# pylontec_mqttinterface1b.net
KiCad netlist of a schematic drawn in EAGLE
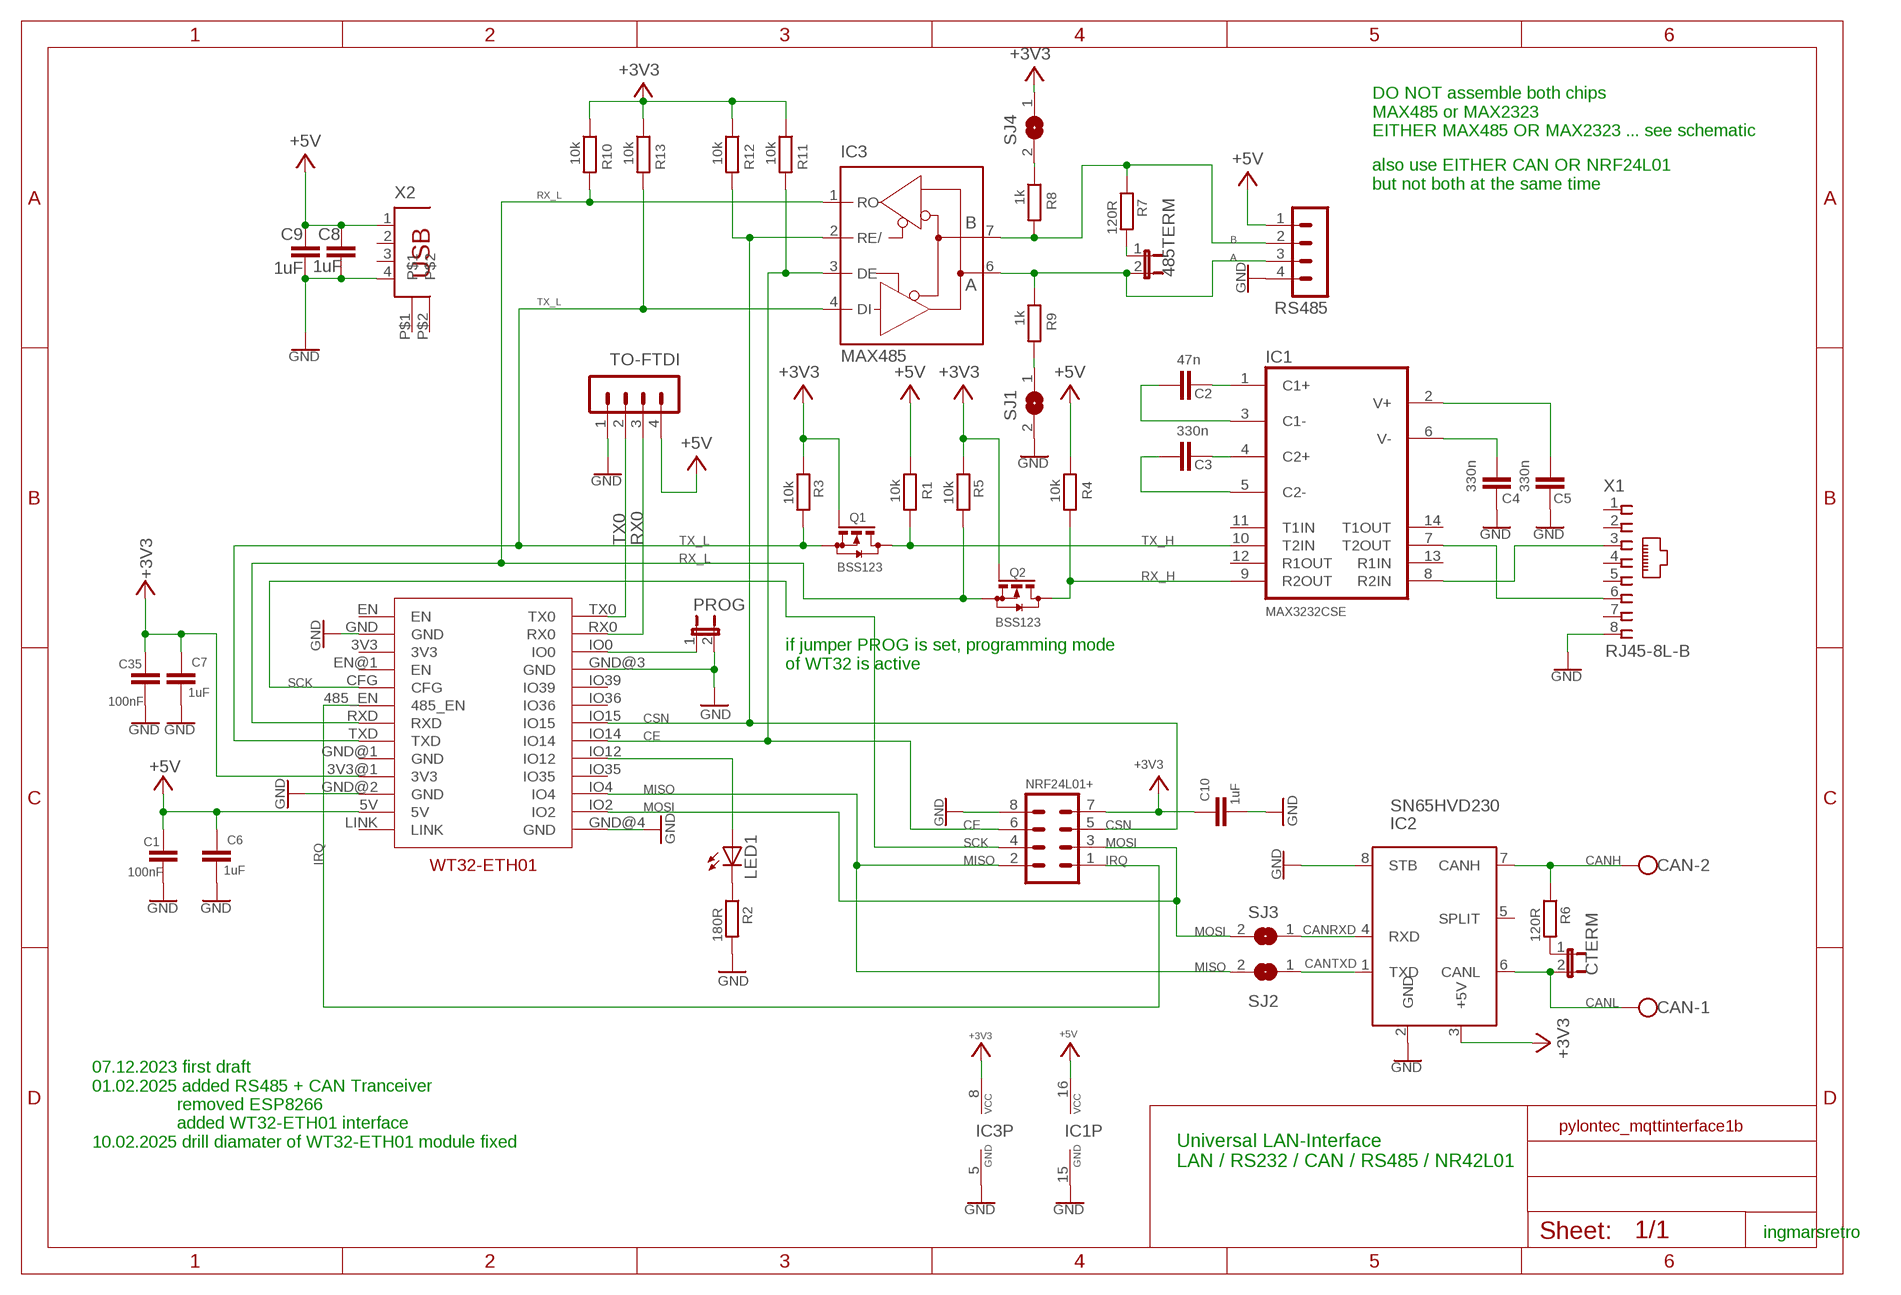
[diagram p0: schematic, sheet 1]

(export (version "E")
  (design (tool "Eeschema 10.0.6"))
  (components
    (comp (ref "485TERM")
      (value "JP1E")
      (footprint "eagle-import:JP1")
      (libsource (lib "eagle-import") (part "JP1E"))
    )
    (comp (ref "C1")
      (value "100nF")
      (footprint "eagle-import:C0805")
      (libsource (lib "eagle-import") (part "resistor_C-EUC0805"))
    )
    (comp (ref "C2")
      (value "47n")
      (footprint "eagle-import:C0805")
      (libsource (lib "eagle-import") (part "resistor_C-EUC0805"))
    )
    (comp (ref "C3")
      (value "330n")
      (footprint "eagle-import:C0805")
      (libsource (lib "eagle-import") (part "resistor_C-EUC0805"))
    )
    (comp (ref "C4")
      (value "330n")
      (footprint "eagle-import:C0805")
      (libsource (lib "eagle-import") (part "resistor_C-EUC0805"))
    )
    (comp (ref "C5")
      (value "330n")
      (footprint "eagle-import:C0805")
      (libsource (lib "eagle-import") (part "resistor_C-EUC0805"))
    )
    (comp (ref "C6")
      (value "1uF")
      (footprint "eagle-import:C1210")
      (libsource (lib "eagle-import") (part "C-EUC1210"))
    )
    (comp (ref "C7")
      (value "1uF")
      (footprint "eagle-import:C1210")
      (libsource (lib "eagle-import") (part "C-EUC1210"))
    )
    (comp (ref "C8")
      (value "1uF")
      (footprint "eagle-import:C1210")
      (libsource (lib "eagle-import") (part "C-EUC1210"))
    )
    (comp (ref "C9")
      (value "1uF")
      (footprint "eagle-import:C1210")
      (libsource (lib "eagle-import") (part "C-EUC1210"))
    )
    (comp (ref "C10")
      (value "1uF")
      (footprint "eagle-import:C1210")
      (libsource (lib "eagle-import") (part "C-EUC1210"))
    )
    (comp (ref "C35")
      (value "100nF")
      (footprint "eagle-import:C0805")
      (libsource (lib "eagle-import") (part "resistor_C-EUC0805"))
    )
    (comp (ref "CAN")
      (value "W237-102")
      (footprint "eagle-import:W237-102")
      (fields (field (name "MPN") "237-102"))
      (libsource (lib "eagle-import") (part "W237-102"))
    )
    (comp (ref "CTERM")
      (value "JP1E")
      (footprint "eagle-import:JP1")
      (libsource (lib "eagle-import") (part "JP1E"))
    )
    (comp (ref "IC1")
      (value "MAX3232CSE")
      (footprint "eagle-import:SO16")
      (libsource (lib "eagle-import") (part "MAX3232SEC"))
    )
    (comp (ref "IC2")
      (value "SN65HVD230")
      (footprint "eagle-import:SO8")
      (libsource (lib "eagle-import") (part "TJA1040"))
    )
    (comp (ref "IC3")
      (value "MAX485")
      (footprint "eagle-import:SO08")
      (fields (field (name "MF") "MAXIM") (field (name "MPN") "MAX481CSA"))
      (libsource (lib "eagle-import") (part "MAX481CSA"))
    )
    (comp (ref "LED1")
      (value "LED_LEDCHIPLED_0805")
      (footprint "eagle-import:LED_CHIPLED_0805")
      (libsource (lib "eagle-import") (part "LED_LEDCHIPLED_0805"))
    )
    (comp (ref "NRF24L01+")
      (value "MA04-2")
      (footprint "eagle-import:MA04-2")
      (libsource (lib "eagle-import") (part "MA04-2"))
    )
    (comp (ref "PROG")
      (value "JP1E")
      (footprint "eagle-import:JP1")
      (libsource (lib "eagle-import") (part "JP1E"))
    )
    (comp (ref "Q1")
      (value "BSS123")
      (footprint "eagle-import:SOT23")
      (libsource (lib "eagle-import") (part "BSS123"))
    )
    (comp (ref "Q2")
      (value "BSS123")
      (footprint "eagle-import:SOT23")
      (libsource (lib "eagle-import") (part "BSS123"))
    )
    (comp (ref "R1")
      (value "10k")
      (footprint "eagle-import:R0805")
      (libsource (lib "eagle-import") (part "R-EU_R0805"))
    )
    (comp (ref "R2")
      (value "180R")
      (footprint "eagle-import:R0805")
      (libsource (lib "eagle-import") (part "R-EU_R0805"))
    )
    (comp (ref "R3")
      (value "10k")
      (footprint "eagle-import:R0805")
      (libsource (lib "eagle-import") (part "R-EU_R0805"))
    )
    (comp (ref "R4")
      (value "10k")
      (footprint "eagle-import:R0805")
      (libsource (lib "eagle-import") (part "R-EU_R0805"))
    )
    (comp (ref "R5")
      (value "10k")
      (footprint "eagle-import:R0805")
      (libsource (lib "eagle-import") (part "R-EU_R0805"))
    )
    (comp (ref "R6")
      (value "120R")
      (footprint "eagle-import:R0805")
      (libsource (lib "eagle-import") (part "R-EU_R0805"))
    )
    (comp (ref "R7")
      (value "120R")
      (footprint "eagle-import:R0805")
      (libsource (lib "eagle-import") (part "R-EU_R0805"))
    )
    (comp (ref "R8")
      (value "1k")
      (footprint "eagle-import:R0805")
      (libsource (lib "eagle-import") (part "R-EU_R0805"))
    )
    (comp (ref "R9")
      (value "1k")
      (footprint "eagle-import:R0805")
      (libsource (lib "eagle-import") (part "R-EU_R0805"))
    )
    (comp (ref "R10")
      (value "10k")
      (footprint "eagle-import:R0805")
      (libsource (lib "eagle-import") (part "R-EU_R0805"))
    )
    (comp (ref "R11")
      (value "10k")
      (footprint "eagle-import:R0805")
      (libsource (lib "eagle-import") (part "R-EU_R0805"))
    )
    (comp (ref "R12")
      (value "10k")
      (footprint "eagle-import:R0805")
      (libsource (lib "eagle-import") (part "R-EU_R0805"))
    )
    (comp (ref "R13")
      (value "10k")
      (footprint "eagle-import:R0805")
      (libsource (lib "eagle-import") (part "R-EU_R0805"))
    )
    (comp (ref "RS485")
      (value "MA04-1")
      (footprint "eagle-import:MA04-1")
      (libsource (lib "eagle-import") (part "MA04-1"))
    )
    (comp (ref "SJ1") (value "SJ") (footprint "eagle-import:SJ") (libsource (lib "eagle-import") (part "SJ")))
    (comp (ref "SJ2") (value "SJ") (footprint "eagle-import:SJ") (libsource (lib "eagle-import") (part "SJ")))
    (comp (ref "SJ3") (value "SJ") (footprint "eagle-import:SJ") (libsource (lib "eagle-import") (part "SJ")))
    (comp (ref "SJ4") (value "SJ") (footprint "eagle-import:SJ") (libsource (lib "eagle-import") (part "SJ")))
    (comp (ref "TO-FTDI")
      (value "MA04-1")
      (footprint "eagle-import:MA04-1")
      (libsource (lib "eagle-import") (part "MA04-1"))
    )
    (comp (ref "U$2")
      (value "WT32-ETH01")
      (footprint "eagle-import:WT32-ETH01")
      (fields (field (name "MF") "wireless-tag"))
      (libsource (lib "eagle-import") (part "WT32-ETH01"))
    )
    (comp (ref "X1")
      (value "RJ45-8L-B")
      (footprint "eagle-import:RJ45-NO-SHIELD")
      (fields (field (name "MF") "TYCO ELECTRONICS"))
      (libsource (lib "eagle-import") (part "RJ45-8L-B"))
    )
    (comp (ref "X2")
      (value "SMARTPRJ_PN61729")
      (footprint "eagle-import:SMARTPRJ_PN61729")
      (libsource (lib "eagle-import") (part "SMARTPRJ_PN61729"))
    )
  )
  (nets
    (net (code "1") (name "+3V3") (class "Default")
      (node (ref "C10") (pin "1") (pinfunction "1_1") (pintype "passive"))
      (node (ref "C35") (pin "2") (pinfunction "2_2") (pintype "passive"))
      (node (ref "C7") (pin "1") (pinfunction "1_1") (pintype "passive"))
      (node (ref "IC2") (pin "3") (pinfunction "+5V_3") (pintype "bidirectional"))
      (node (ref "IC3") (pin "8") (pinfunction "VCC_8") (pintype "power_in"))
      (node (ref "NRF24L01+") (pin "7") (pinfunction "7_7") (pintype "passive"))
      (node (ref "Q1") (pin "1") (pinfunction "G_1") (pintype "passive"))
      (node (ref "Q2") (pin "1") (pinfunction "G_1") (pintype "passive"))
      (node (ref "R10") (pin "1") (pinfunction "1_1") (pintype "passive"))
      (node (ref "R11") (pin "1") (pinfunction "1_1") (pintype "passive"))
      (node (ref "R12") (pin "1") (pinfunction "1_1") (pintype "passive"))
      (node (ref "R13") (pin "1") (pinfunction "1_1") (pintype "passive"))
      (node (ref "R3") (pin "1") (pinfunction "1_1") (pintype "passive"))
      (node (ref "R5") (pin "1") (pinfunction "1_1") (pintype "passive"))
      (node (ref "SJ4") (pin "1") (pinfunction "1_1") (pintype "passive"))
      (node (ref "U$2") (pin "3V3@1") (pinfunction "3V3_3V3@1") (pintype "bidirectional"))
    )
    (net (code "2") (name "+5V") (class "Default")
      (node (ref "C1") (pin "2") (pinfunction "2_2") (pintype "passive"))
      (node (ref "C6") (pin "1") (pinfunction "1_1") (pintype "passive"))
      (node (ref "C8") (pin "1") (pinfunction "1_1") (pintype "passive"))
      (node (ref "C9") (pin "1") (pinfunction "1_1") (pintype "passive"))
      (node (ref "IC1") (pin "16") (pinfunction "VCC_16") (pintype "power_in"))
      (node (ref "R1") (pin "1") (pinfunction "1_1") (pintype "passive"))
      (node (ref "R4") (pin "1") (pinfunction "1_1") (pintype "passive"))
      (node (ref "RS485") (pin "1") (pinfunction "1_1") (pintype "passive"))
      (node (ref "TO-FTDI") (pin "4") (pinfunction "4_4") (pintype "passive"))
      (node (ref "U$2") (pin "5V") (pinfunction "5V_5V") (pintype "bidirectional"))
      (node (ref "X2") (pin "1") (pinfunction "1_1") (pintype "bidirectional"))
    )
    (net (code "3") (name "/A") (class "Default")
      (node (ref "485TERM") (pin "2") (pinfunction "2_2") (pintype "passive"))
      (node (ref "IC3") (pin "6") (pinfunction "A_6") (pintype "passive"))
      (node (ref "R9") (pin "1") (pinfunction "1_1") (pintype "passive"))
      (node (ref "RS485") (pin "3") (pinfunction "3_3") (pintype "passive"))
    )
    (net (code "4") (name "/B") (class "Default")
      (node (ref "IC3") (pin "7") (pinfunction "B_7") (pintype "passive"))
      (node (ref "R7") (pin "1") (pinfunction "1_1") (pintype "passive"))
      (node (ref "R8") (pin "2") (pinfunction "2_2") (pintype "passive"))
      (node (ref "RS485") (pin "2") (pinfunction "2_2") (pintype "passive"))
    )
    (net (code "5") (name "/CANH") (class "Default")
      (node (ref "CAN") (pin "2") (pinfunction "KL_2") (pintype "passive"))
      (node (ref "IC2") (pin "7") (pinfunction "CANH_7") (pintype "bidirectional"))
      (node (ref "R6") (pin "1") (pinfunction "1_1") (pintype "passive"))
    )
    (net (code "6") (name "/CANL") (class "Default")
      (node (ref "CAN") (pin "1") (pinfunction "KL_1") (pintype "passive"))
      (node (ref "CTERM") (pin "2") (pinfunction "2_2") (pintype "passive"))
      (node (ref "IC2") (pin "6") (pinfunction "CANL_6") (pintype "bidirectional"))
    )
    (net (code "7") (name "/CANRXD") (class "Default")
      (node (ref "IC2") (pin "4") (pinfunction "RXD_4") (pintype "bidirectional"))
      (node (ref "SJ3") (pin "1") (pinfunction "1_1") (pintype "passive"))
    )
    (net (code "8") (name "/CANTXD") (class "Default")
      (node (ref "IC2") (pin "1") (pinfunction "TXD_1") (pintype "bidirectional"))
      (node (ref "SJ2") (pin "1") (pinfunction "1_1") (pintype "passive"))
    )
    (net (code "9") (name "/CE") (class "Default")
      (node (ref "IC3") (pin "3") (pinfunction "DE_3") (pintype "input"))
      (node (ref "NRF24L01+") (pin "6") (pinfunction "6_6") (pintype "passive"))
      (node (ref "R11") (pin "2") (pinfunction "2_2") (pintype "passive"))
      (node (ref "U$2") (pin "IO14") (pinfunction "IO14_IO14") (pintype "bidirectional"))
    )
    (net (code "10") (name "/CSN") (class "Default")
      (node (ref "IC3") (pin "2") (pinfunction "RE/_2") (pintype "input"))
      (node (ref "NRF24L01+") (pin "5") (pinfunction "5_5") (pintype "passive"))
      (node (ref "R12") (pin "2") (pinfunction "2_2") (pintype "passive"))
      (node (ref "U$2") (pin "IO15") (pinfunction "IO15_IO15") (pintype "bidirectional"))
    )
    (net (code "11") (name "/IRQ") (class "Default")
      (node (ref "NRF24L01+") (pin "1") (pinfunction "1_1") (pintype "passive"))
      (node (ref "U$2") (pin "485_EN") (pinfunction "485_EN_485_EN") (pintype "bidirectional"))
    )
    (net (code "12") (name "/MISO") (class "Default")
      (node (ref "NRF24L01+") (pin "2") (pinfunction "2_2") (pintype "passive"))
      (node (ref "SJ2") (pin "2") (pinfunction "2_2") (pintype "passive"))
      (node (ref "U$2") (pin "IO4") (pinfunction "IO4_IO4") (pintype "bidirectional"))
    )
    (net (code "13") (name "/MOSI") (class "Default")
      (node (ref "NRF24L01+") (pin "3") (pinfunction "3_3") (pintype "passive"))
      (node (ref "SJ3") (pin "2") (pinfunction "2_2") (pintype "passive"))
      (node (ref "U$2") (pin "IO2") (pinfunction "IO2_IO2") (pintype "bidirectional"))
    )
    (net (code "14") (name "/RX0") (class "Default")
      (node (ref "TO-FTDI") (pin "3") (pinfunction "3_3") (pintype "passive"))
      (node (ref "U$2") (pin "RX0") (pinfunction "RX0_RX0") (pintype "bidirectional"))
    )
    (net (code "15") (name "/RX_H") (class "Default")
      (node (ref "IC1") (pin "9") (pinfunction "R2OUT_9") (pintype "output"))
      (node (ref "Q2") (pin "3") (pinfunction "D_3") (pintype "passive"))
      (node (ref "R4") (pin "2") (pinfunction "2_2") (pintype "passive"))
    )
    (net (code "16") (name "/RX_L") (class "Default")
      (node (ref "IC3") (pin "1") (pinfunction "RO_1") (pintype "output"))
      (node (ref "Q2") (pin "2") (pinfunction "S_2") (pintype "passive"))
      (node (ref "R10") (pin "2") (pinfunction "2_2") (pintype "passive"))
      (node (ref "R5") (pin "2") (pinfunction "2_2") (pintype "passive"))
      (node (ref "U$2") (pin "RXD") (pinfunction "RXD_RXD") (pintype "bidirectional"))
    )
    (net (code "17") (name "/SCK") (class "Default")
      (node (ref "NRF24L01+") (pin "4") (pinfunction "4_4") (pintype "passive"))
      (node (ref "U$2") (pin "CFG") (pinfunction "CFG_CFG") (pintype "bidirectional"))
    )
    (net (code "18") (name "/TX0") (class "Default")
      (node (ref "TO-FTDI") (pin "2") (pinfunction "2_2") (pintype "passive"))
      (node (ref "U$2") (pin "TX0") (pinfunction "TX0_TX0") (pintype "bidirectional"))
    )
    (net (code "19") (name "/TX_H") (class "Default")
      (node (ref "IC1") (pin "10") (pinfunction "T2IN_10") (pintype "input"))
      (node (ref "Q1") (pin "3") (pinfunction "D_3") (pintype "passive"))
      (node (ref "R1") (pin "2") (pinfunction "2_2") (pintype "passive"))
    )
    (net (code "20") (name "/TX_L") (class "Default")
      (node (ref "IC3") (pin "4") (pinfunction "DI_4") (pintype "input"))
      (node (ref "Q1") (pin "2") (pinfunction "S_2") (pintype "passive"))
      (node (ref "R13") (pin "2") (pinfunction "2_2") (pintype "passive"))
      (node (ref "R3") (pin "2") (pinfunction "2_2") (pintype "passive"))
      (node (ref "U$2") (pin "TXD") (pinfunction "TXD_TXD") (pintype "bidirectional"))
    )
    (net (code "21") (name "GND") (class "Default")
      (node (ref "C1") (pin "1") (pinfunction "1_1") (pintype "passive"))
      (node (ref "C10") (pin "2") (pinfunction "2_2") (pintype "passive"))
      (node (ref "C35") (pin "1") (pinfunction "1_1") (pintype "passive"))
      (node (ref "C4") (pin "2") (pinfunction "2_2") (pintype "passive"))
      (node (ref "C5") (pin "2") (pinfunction "2_2") (pintype "passive"))
      (node (ref "C6") (pin "2") (pinfunction "2_2") (pintype "passive"))
      (node (ref "C7") (pin "2") (pinfunction "2_2") (pintype "passive"))
      (node (ref "C8") (pin "2") (pinfunction "2_2") (pintype "passive"))
      (node (ref "C9") (pin "2") (pinfunction "2_2") (pintype "passive"))
      (node (ref "IC1") (pin "15") (pinfunction "GND_15") (pintype "power_in"))
      (node (ref "IC2") (pin "2") (pinfunction "GND_2") (pintype "bidirectional"))
      (node (ref "IC2") (pin "8") (pinfunction "STB_8") (pintype "bidirectional"))
      (node (ref "IC3") (pin "5") (pinfunction "GND_5") (pintype "power_in"))
      (node (ref "NRF24L01+") (pin "8") (pinfunction "8_8") (pintype "passive"))
      (node (ref "PROG") (pin "2") (pinfunction "2_2") (pintype "passive"))
      (node (ref "R2") (pin "2") (pinfunction "2_2") (pintype "passive"))
      (node (ref "RS485") (pin "4") (pinfunction "4_4") (pintype "passive"))
      (node (ref "SJ1") (pin "2") (pinfunction "2_2") (pintype "passive"))
      (node (ref "TO-FTDI") (pin "1") (pinfunction "1_1") (pintype "passive"))
      (node (ref "U$2") (pin "GND") (pinfunction "GND_GND") (pintype "bidirectional"))
      (node (ref "U$2") (pin "GND@2") (pinfunction "GND_GND@2") (pintype "bidirectional"))
      (node (ref "U$2") (pin "GND@3") (pinfunction "GND_GND@3") (pintype "bidirectional"))
      (node (ref "U$2") (pin "GND@4") (pinfunction "GND_GND@4") (pintype "bidirectional"))
      (node (ref "X1") (pin "8") (pinfunction "8_8") (pintype "passive"))
      (node (ref "X2") (pin "4") (pinfunction "4_4") (pintype "bidirectional"))
    )
    (net (code "22") (name "Net-(485TERM-Pad1)") (class "Default")
      (node (ref "485TERM") (pin "1") (pinfunction "1_1") (pintype "passive"))
      (node (ref "R7") (pin "2") (pinfunction "2_2") (pintype "passive"))
    )
    (net (code "23") (name "Net-(CTERM-Pad1)") (class "Default")
      (node (ref "CTERM") (pin "1") (pinfunction "1_1") (pintype "passive"))
      (node (ref "R6") (pin "2") (pinfunction "2_2") (pintype "passive"))
    )
    (net (code "24") (name "Net-(IC1A-C1+)") (class "Default")
      (node (ref "C2") (pin "1") (pinfunction "1_1") (pintype "passive"))
      (node (ref "IC1") (pin "1") (pinfunction "C1+_1") (pintype "bidirectional"))
    )
    (net (code "25") (name "Net-(IC1A-C1-)") (class "Default")
      (node (ref "C2") (pin "2") (pinfunction "2_2") (pintype "passive"))
      (node (ref "IC1") (pin "3") (pinfunction "C1-_3") (pintype "bidirectional"))
    )
    (net (code "26") (name "Net-(IC1A-C2+)") (class "Default")
      (node (ref "C3") (pin "1") (pinfunction "1_1") (pintype "passive"))
      (node (ref "IC1") (pin "4") (pinfunction "C2+_4") (pintype "bidirectional"))
    )
    (net (code "27") (name "Net-(IC1A-C2-)") (class "Default")
      (node (ref "C3") (pin "2") (pinfunction "2_2") (pintype "passive"))
      (node (ref "IC1") (pin "5") (pinfunction "C2-_5") (pintype "bidirectional"))
    )
    (net (code "28") (name "Net-(IC1A-R2IN)") (class "Default")
      (node (ref "IC1") (pin "8") (pinfunction "R2IN_8") (pintype "input"))
      (node (ref "X1") (pin "3") (pinfunction "3_3") (pintype "passive"))
    )
    (net (code "29") (name "Net-(IC1A-T2OUT)") (class "Default")
      (node (ref "IC1") (pin "7") (pinfunction "T2OUT_7") (pintype "output"))
      (node (ref "X1") (pin "6") (pinfunction "6_6") (pintype "passive"))
    )
    (net (code "30") (name "Net-(IC1A-V+)") (class "Default")
      (node (ref "C5") (pin "1") (pinfunction "1_1") (pintype "passive"))
      (node (ref "IC1") (pin "2") (pinfunction "V+_2") (pintype "bidirectional"))
    )
    (net (code "31") (name "Net-(IC1A-V-)") (class "Default")
      (node (ref "C4") (pin "1") (pinfunction "1_1") (pintype "passive"))
      (node (ref "IC1") (pin "6") (pinfunction "V-_6") (pintype "bidirectional"))
    )
    (net (code "32") (name "Net-(LED1-PadA)") (class "Default")
      (node (ref "LED1") (pin "A") (pinfunction "A_A") (pintype "passive"))
      (node (ref "U$2") (pin "IO12") (pinfunction "IO12_IO12") (pintype "bidirectional"))
    )
    (net (code "33") (name "Net-(LED1-PadC)") (class "Default")
      (node (ref "LED1") (pin "C") (pinfunction "C_C") (pintype "passive"))
      (node (ref "R2") (pin "1") (pinfunction "1_1") (pintype "passive"))
    )
    (net (code "34") (name "Net-(PROG-Pad1)") (class "Default")
      (node (ref "PROG") (pin "1") (pinfunction "1_1") (pintype "passive"))
      (node (ref "U$2") (pin "IO0") (pinfunction "IO0_IO0") (pintype "bidirectional"))
    )
    (net (code "35") (name "Net-(R8-Pad1)") (class "Default")
      (node (ref "R8") (pin "1") (pinfunction "1_1") (pintype "passive"))
      (node (ref "SJ4") (pin "2") (pinfunction "2_2") (pintype "passive"))
    )
    (net (code "36") (name "Net-(R9-Pad2)") (class "Default")
      (node (ref "R9") (pin "2") (pinfunction "2_2") (pintype "passive"))
      (node (ref "SJ1") (pin "1") (pinfunction "1_1") (pintype "passive"))
    )
    (net (code "37") (name "unconnected-(IC1A-R1IN-Pad13)") (class "Default")
      (node (ref "IC1") (pin "13") (pinfunction "R1IN_13") (pintype "input"))
    )
    (net (code "38") (name "unconnected-(IC1A-R1OUT-Pad12)") (class "Default")
      (node (ref "IC1") (pin "12") (pinfunction "R1OUT_12") (pintype "output"))
    )
    (net (code "39") (name "unconnected-(IC1A-T1IN-Pad11)") (class "Default")
      (node (ref "IC1") (pin "11") (pinfunction "T1IN_11") (pintype "input"))
    )
    (net (code "40") (name "unconnected-(IC1A-T1OUT-Pad14)") (class "Default")
      (node (ref "IC1") (pin "14") (pinfunction "T1OUT_14") (pintype "output"))
    )
    (net (code "41") (name "unconnected-(IC2-SPLIT-Pad5)") (class "Default")
      (node (ref "IC2") (pin "5") (pinfunction "SPLIT_5") (pintype "bidirectional"))
    )
    (net (code "42") (name "unconnected-(U$2-EN-PadEN@1)") (class "Default")
      (node (ref "U$2") (pin "EN@1") (pinfunction "EN_EN@1") (pintype "bidirectional"))
    )
    (net (code "43") (name "unconnected-(U$2-GND-PadGND@1)") (class "Default")
      (node (ref "U$2") (pin "GND@1") (pinfunction "GND_GND@1") (pintype "bidirectional"))
    )
    (net (code "44") (name "unconnected-(U$2-Pad3V3)") (class "Default")
      (node (ref "U$2") (pin "3V3") (pinfunction "3V3_3V3") (pintype "bidirectional"))
    )
    (net (code "45") (name "unconnected-(U$2-PadEN)") (class "Default")
      (node (ref "U$2") (pin "EN") (pinfunction "EN_EN") (pintype "bidirectional"))
    )
    (net (code "46") (name "unconnected-(U$2-PadIO35)") (class "Default")
      (node (ref "U$2") (pin "IO35") (pinfunction "IO35_IO35") (pintype "bidirectional"))
    )
    (net (code "47") (name "unconnected-(U$2-PadIO36)") (class "Default")
      (node (ref "U$2") (pin "IO36") (pinfunction "IO36_IO36") (pintype "bidirectional"))
    )
    (net (code "48") (name "unconnected-(U$2-PadIO39)") (class "Default")
      (node (ref "U$2") (pin "IO39") (pinfunction "IO39_IO39") (pintype "bidirectional"))
    )
    (net (code "49") (name "unconnected-(U$2-PadLINK)") (class "Default")
      (node (ref "U$2") (pin "LINK") (pinfunction "LINK_LINK") (pintype "bidirectional"))
    )
    (net (code "50") (name "unconnected-(X1-Pad1)") (class "Default")
      (node (ref "X1") (pin "1") (pinfunction "1_1") (pintype "passive"))
    )
    (net (code "51") (name "unconnected-(X1-Pad2)") (class "Default")
      (node (ref "X1") (pin "2") (pinfunction "2_2") (pintype "passive"))
    )
    (net (code "52") (name "unconnected-(X1-Pad4)") (class "Default")
      (node (ref "X1") (pin "4") (pinfunction "4_4") (pintype "passive"))
    )
    (net (code "53") (name "unconnected-(X1-Pad5)") (class "Default")
      (node (ref "X1") (pin "5") (pinfunction "5_5") (pintype "passive"))
    )
    (net (code "54") (name "unconnected-(X1-Pad7)") (class "Default")
      (node (ref "X1") (pin "7") (pinfunction "7_7") (pintype "passive"))
    )
    (net (code "55") (name "unconnected-(X2-Pad2)") (class "Default")
      (node (ref "X2") (pin "2") (pinfunction "2_2") (pintype "bidirectional"))
    )
    (net (code "56") (name "unconnected-(X2-Pad3)") (class "Default")
      (node (ref "X2") (pin "3") (pinfunction "3_3") (pintype "bidirectional"))
    )
    (net (code "57") (name "unconnected-(X2-PadP$1)") (class "Default")
      (node (ref "X2") (pin "P$1") (pinfunction "P$1_P$1") (pintype "bidirectional"))
    )
    (net (code "58") (name "unconnected-(X2-PadP$2)") (class "Default")
      (node (ref "X2") (pin "P$2") (pinfunction "P$2_P$2") (pintype "bidirectional"))
    )
  )
)
